# main.net
KiCad netlist of a schematic drawn in EAGLE
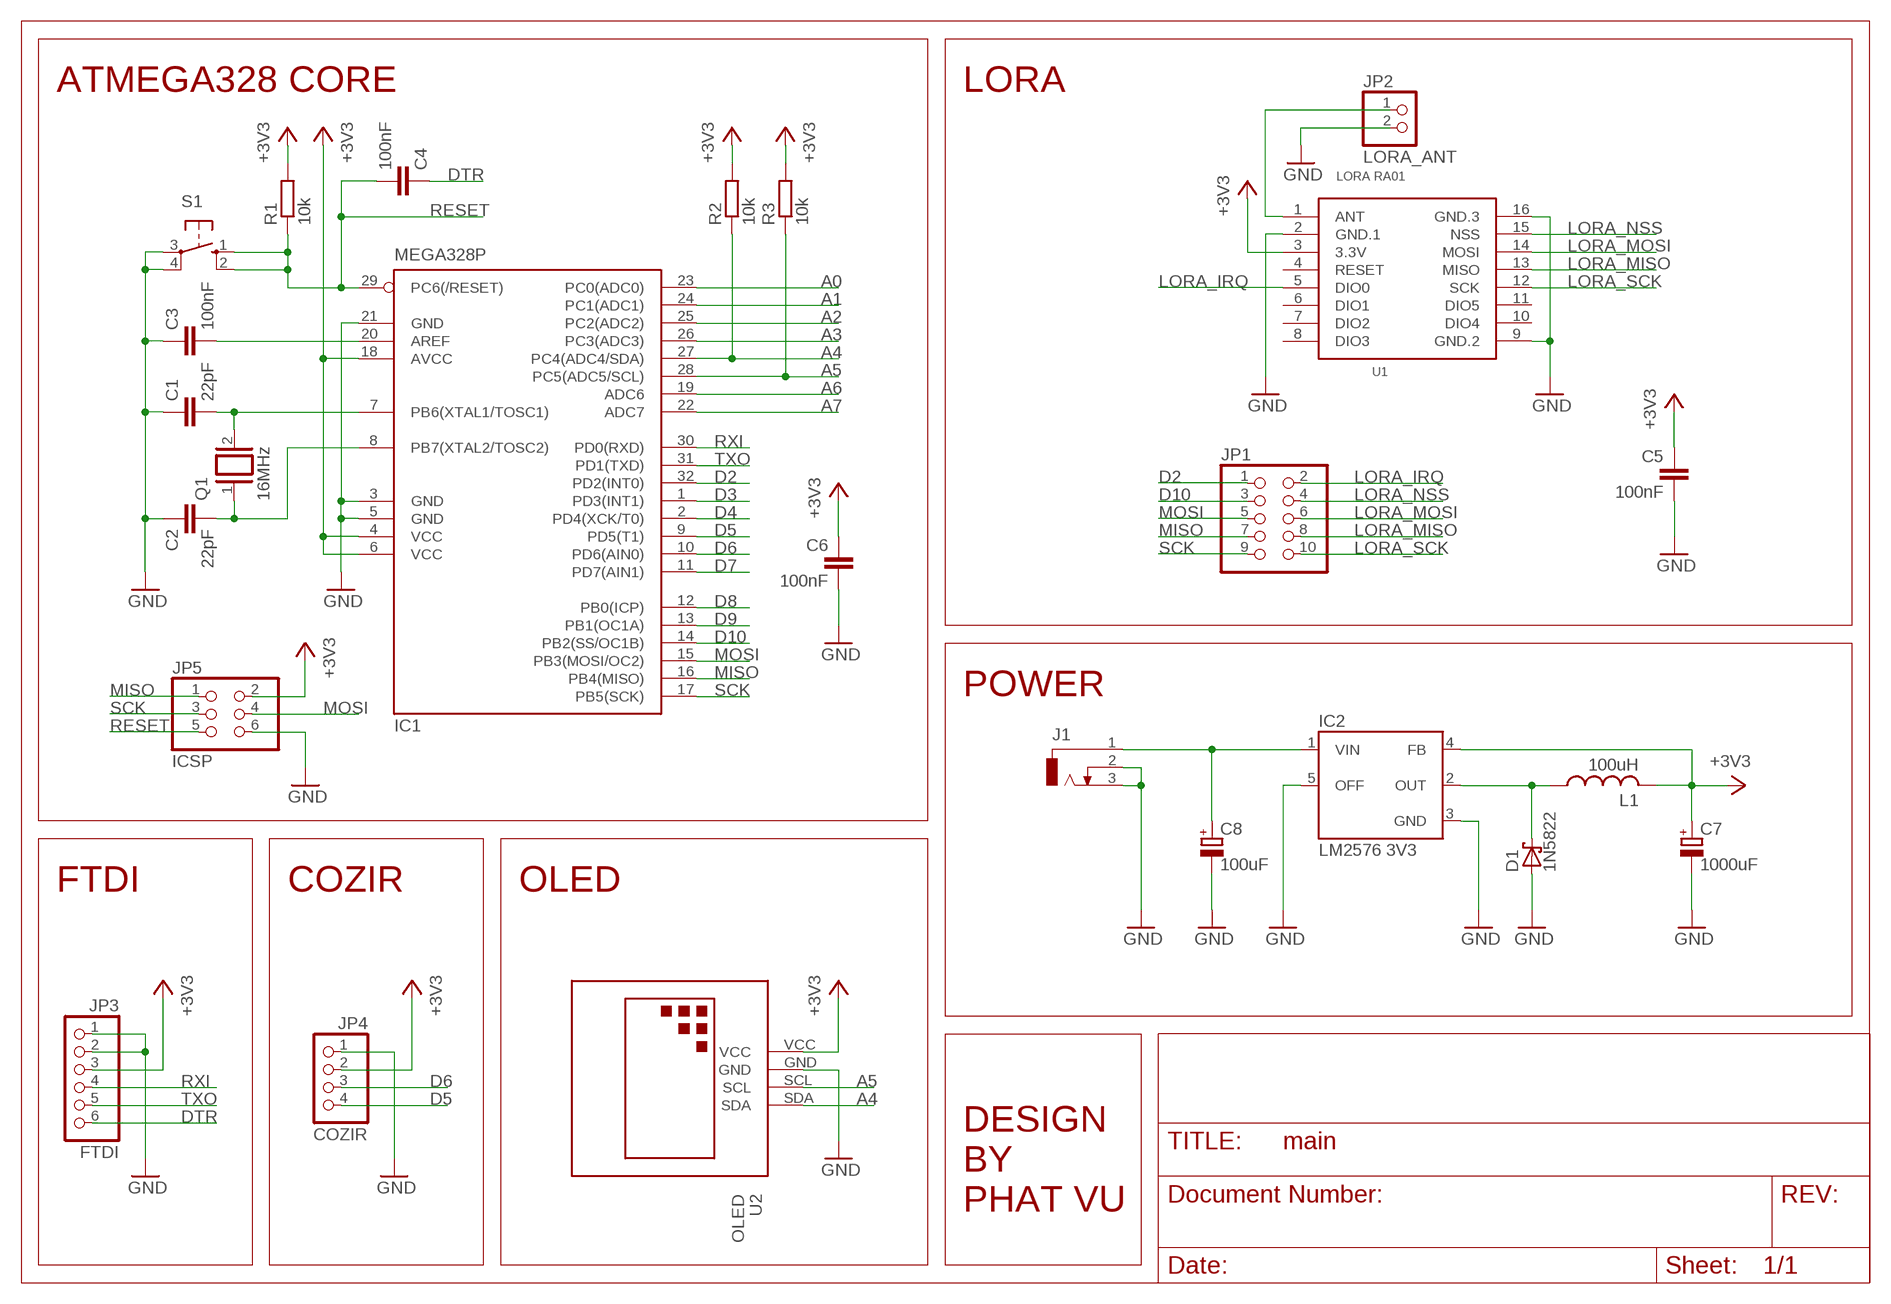
[diagram p0: schematic, sheet 1]

(export (version "E")
  (design (tool "Eeschema 10.0.6"))
  (components
    (comp (ref "C1")
      (value "22pF")
      (footprint "eagle-import:C050-024X044")
      (libsource (lib "eagle-import") (part "C-EU050-024X044"))
    )
    (comp (ref "C2")
      (value "22pF")
      (footprint "eagle-import:C050-024X044")
      (libsource (lib "eagle-import") (part "C-EU050-024X044"))
    )
    (comp (ref "C3")
      (value "100nF")
      (footprint "eagle-import:C050-024X044")
      (libsource (lib "eagle-import") (part "C-EU050-024X044"))
    )
    (comp (ref "C4")
      (value "100nF")
      (footprint "eagle-import:C050-024X044")
      (libsource (lib "eagle-import") (part "C-EU050-024X044"))
    )
    (comp (ref "C5")
      (value "100nF")
      (footprint "eagle-import:C050-024X044")
      (libsource (lib "eagle-import") (part "C-EU050-024X044"))
    )
    (comp (ref "C6")
      (value "100nF")
      (footprint "eagle-import:C050-024X044")
      (libsource (lib "eagle-import") (part "C-EU050-024X044"))
    )
    (comp (ref "C7")
      (value "1000uF")
      (footprint "eagle-import:E5-13")
      (libsource (lib "eagle-import") (part "CPOL-EUE5-13"))
    )
    (comp (ref "C8")
      (value "100uF")
      (footprint "eagle-import:E5-8,5")
      (libsource (lib "eagle-import") (part "CPOL-EUE5-8.5"))
    )
    (comp (ref "D1")
      (value "1N5822")
      (footprint "eagle-import:DO201T15")
      (libsource (lib "eagle-import") (part "SCHOTTKY-DIODEDO201T15"))
    )
    (comp (ref "IC1")
      (value "MEGA328P")
      (footprint "eagle-import:TQFP32-08")
      (fields (field (name "MPN") "ATMEGA8-16AU"))
      (libsource (lib "eagle-import") (part "MEGA8-AI"))
    )
    (comp (ref "IC2")
      (value "LM2576 3V3")
      (footprint "eagle-import:TO263-5")
      (libsource (lib "eagle-import") (part "LM2576S"))
    )
    (comp (ref "J1")
      (value "DCJ0303")
      (footprint "eagle-import:DCJ0303")
      (libsource (lib "eagle-import") (part "DCJ0303"))
    )
    (comp (ref "JP1")
      (value "PINHD-2X5")
      (footprint "eagle-import:2X05")
      (libsource (lib "eagle-import") (part "PINHD-2X5"))
    )
    (comp (ref "JP2")
      (value "LORA_ANT")
      (footprint "eagle-import:1X02")
      (libsource (lib "eagle-import") (part "PINHD-1X2"))
    )
    (comp (ref "JP3")
      (value "FTDI")
      (footprint "eagle-import:1X06")
      (libsource (lib "eagle-import") (part "PINHD-1X6"))
    )
    (comp (ref "JP4")
      (value "COZIR")
      (footprint "eagle-import:1X04")
      (libsource (lib "eagle-import") (part "PINHD-1X4"))
    )
    (comp (ref "JP5")
      (value "ICSP")
      (footprint "eagle-import:2X03")
      (libsource (lib "eagle-import") (part "PINHD-2X3"))
    )
    (comp (ref "L1")
      (value "100uH")
      (footprint "eagle-import:6000-XXXX-RC")
      (libsource (lib "eagle-import") (part "L-US6000-XXX-RC"))
    )
    (comp (ref "Q1")
      (value "16MHz")
      (footprint "eagle-import:QS")
      (libsource (lib "eagle-import") (part "XTAL/S"))
    )
    (comp (ref "R1")
      (value "10k")
      (footprint "eagle-import:0207_10")
      (libsource (lib "eagle-import") (part "R-EU_0207/10"))
    )
    (comp (ref "R2")
      (value "10k")
      (footprint "eagle-import:0207_10")
      (libsource (lib "eagle-import") (part "R-EU_0207/10"))
    )
    (comp (ref "R3")
      (value "10k")
      (footprint "eagle-import:0207_10")
      (libsource (lib "eagle-import") (part "R-EU_0207/10"))
    )
    (comp (ref "S1")
      (value "10-XX")
      (footprint "eagle-import:B3F-10XX")
      (fields (field (name "MPN") "B3F-1000"))
      (libsource (lib "eagle-import") (part "10-XX"))
    )
    (comp (ref "U1")
      (value "LORA RA01")
      (footprint "eagle-import:LORA-RA1-SMD")
      (libsource (lib "eagle-import") (part "LORA-RA-01-433MHZ"))
    )
    (comp (ref "U2")
      (value "OLED")
      (footprint "eagle-import:OLED-096-I2C")
      (libsource (lib "eagle-import") (part "OLED-096-I2C"))
    )
  )
  (nets
    (net (code "1") (name "+3V3") (class "Default")
      (node (ref "C5") (pin "1") (pinfunction "1_1") (pintype "passive"))
      (node (ref "C6") (pin "1") (pinfunction "1_1") (pintype "passive"))
      (node (ref "C7") (pin "+") (pinfunction "+_+") (pintype "passive"))
      (node (ref "IC1") (pin "18") (pinfunction "AVCC_18") (pintype "power_in"))
      (node (ref "IC1") (pin "4") (pinfunction "VCC_4") (pintype "power_in"))
      (node (ref "IC1") (pin "6") (pinfunction "VCC_6") (pintype "power_in"))
      (node (ref "IC2") (pin "4") (pinfunction "FB_4") (pintype "input"))
      (node (ref "JP3") (pin "3") (pinfunction "3_3") (pintype "passive"))
      (node (ref "JP4") (pin "2") (pinfunction "2_2") (pintype "passive"))
      (node (ref "JP5") (pin "2") (pinfunction "2_2") (pintype "passive"))
      (node (ref "L1") (pin "2") (pinfunction "2_2") (pintype "passive"))
      (node (ref "R1") (pin "2") (pinfunction "2_2") (pintype "passive"))
      (node (ref "R2") (pin "2") (pinfunction "2_2") (pintype "passive"))
      (node (ref "R3") (pin "2") (pinfunction "2_2") (pintype "passive"))
      (node (ref "U1") (pin "3") (pinfunction "3.3V_3") (pintype "power_in"))
      (node (ref "U2") (pin "VCC") (pinfunction "VCC_VCC") (pintype "power_in"))
    )
    (net (code "2") (name "/A0") (class "Default")
      (node (ref "IC1") (pin "23") (pinfunction "PC0(ADC0)_23") (pintype "bidirectional"))
    )
    (net (code "3") (name "/A1") (class "Default")
      (node (ref "IC1") (pin "24") (pinfunction "PC1(ADC1)_24") (pintype "bidirectional"))
    )
    (net (code "4") (name "/A2") (class "Default")
      (node (ref "IC1") (pin "25") (pinfunction "PC2(ADC2)_25") (pintype "bidirectional"))
    )
    (net (code "5") (name "/A3") (class "Default")
      (node (ref "IC1") (pin "26") (pinfunction "PC3(ADC3)_26") (pintype "bidirectional"))
    )
    (net (code "6") (name "/A4") (class "Default")
      (node (ref "IC1") (pin "27") (pinfunction "PC4(ADC4/SDA)_27") (pintype "bidirectional"))
      (node (ref "R2") (pin "1") (pinfunction "1_1") (pintype "passive"))
      (node (ref "U2") (pin "SDA") (pinfunction "SDA_SDA") (pintype "bidirectional"))
    )
    (net (code "7") (name "/A5") (class "Default")
      (node (ref "IC1") (pin "28") (pinfunction "PC5(ADC5/SCL)_28") (pintype "bidirectional"))
      (node (ref "R3") (pin "1") (pinfunction "1_1") (pintype "passive"))
      (node (ref "U2") (pin "SCL") (pinfunction "SCL_SCL") (pintype "bidirectional"))
    )
    (net (code "8") (name "/A6") (class "Default")
      (node (ref "IC1") (pin "19") (pinfunction "ADC6_19") (pintype "bidirectional"))
    )
    (net (code "9") (name "/A7") (class "Default")
      (node (ref "IC1") (pin "22") (pinfunction "ADC7_22") (pintype "bidirectional"))
    )
    (net (code "10") (name "/D2") (class "Default")
      (node (ref "IC1") (pin "32") (pinfunction "PD2(INT0)_32") (pintype "bidirectional"))
      (node (ref "JP1") (pin "1") (pinfunction "1_1") (pintype "passive"))
    )
    (net (code "11") (name "/D3") (class "Default")
      (node (ref "IC1") (pin "1") (pinfunction "PD3(INT1)_1") (pintype "bidirectional"))
    )
    (net (code "12") (name "/D4") (class "Default")
      (node (ref "IC1") (pin "2") (pinfunction "PD4(XCK/T0)_2") (pintype "bidirectional"))
    )
    (net (code "13") (name "/D5") (class "Default")
      (node (ref "IC1") (pin "9") (pinfunction "PD5(T1)_9") (pintype "bidirectional"))
      (node (ref "JP4") (pin "4") (pinfunction "4_4") (pintype "passive"))
    )
    (net (code "14") (name "/D6") (class "Default")
      (node (ref "IC1") (pin "10") (pinfunction "PD6(AIN0)_10") (pintype "bidirectional"))
      (node (ref "JP4") (pin "3") (pinfunction "3_3") (pintype "passive"))
    )
    (net (code "15") (name "/D7") (class "Default")
      (node (ref "IC1") (pin "11") (pinfunction "PD7(AIN1)_11") (pintype "bidirectional"))
    )
    (net (code "16") (name "/D8") (class "Default")
      (node (ref "IC1") (pin "12") (pinfunction "PB0(ICP)_12") (pintype "bidirectional"))
    )
    (net (code "17") (name "/D9") (class "Default")
      (node (ref "IC1") (pin "13") (pinfunction "PB1(OC1A)_13") (pintype "bidirectional"))
    )
    (net (code "18") (name "/D10") (class "Default")
      (node (ref "IC1") (pin "14") (pinfunction "PB2(SS/OC1B)_14") (pintype "bidirectional"))
      (node (ref "JP1") (pin "3") (pinfunction "3_3") (pintype "passive"))
    )
    (net (code "19") (name "/DTR") (class "Default")
      (node (ref "C4") (pin "1") (pinfunction "1_1") (pintype "passive"))
      (node (ref "JP3") (pin "6") (pinfunction "6_6") (pintype "passive"))
    )
    (net (code "20") (name "/LORA_IRQ") (class "Default")
      (node (ref "JP1") (pin "2") (pinfunction "2_2") (pintype "passive"))
      (node (ref "U1") (pin "5") (pinfunction "DIO0_5") (pintype "bidirectional"))
    )
    (net (code "21") (name "/LORA_MISO") (class "Default")
      (node (ref "JP1") (pin "8") (pinfunction "8_8") (pintype "passive"))
      (node (ref "U1") (pin "13") (pinfunction "MISO_13") (pintype "bidirectional"))
    )
    (net (code "22") (name "/LORA_MOSI") (class "Default")
      (node (ref "JP1") (pin "6") (pinfunction "6_6") (pintype "passive"))
      (node (ref "U1") (pin "14") (pinfunction "MOSI_14") (pintype "bidirectional"))
    )
    (net (code "23") (name "/LORA_NSS") (class "Default")
      (node (ref "JP1") (pin "4") (pinfunction "4_4") (pintype "passive"))
      (node (ref "U1") (pin "15") (pinfunction "NSS_15") (pintype "bidirectional"))
    )
    (net (code "24") (name "/LORA_SCK") (class "Default")
      (node (ref "JP1") (pin "10") (pinfunction "10_10") (pintype "passive"))
      (node (ref "U1") (pin "12") (pinfunction "SCK_12") (pintype "bidirectional"))
    )
    (net (code "25") (name "/MISO") (class "Default")
      (node (ref "IC1") (pin "16") (pinfunction "PB4(MISO)_16") (pintype "bidirectional"))
      (node (ref "JP1") (pin "7") (pinfunction "7_7") (pintype "passive"))
      (node (ref "JP5") (pin "1") (pinfunction "1_1") (pintype "passive"))
    )
    (net (code "26") (name "/MOSI") (class "Default")
      (node (ref "IC1") (pin "15") (pinfunction "PB3(MOSI/OC2)_15") (pintype "bidirectional"))
      (node (ref "JP1") (pin "5") (pinfunction "5_5") (pintype "passive"))
      (node (ref "JP5") (pin "4") (pinfunction "4_4") (pintype "passive"))
    )
    (net (code "27") (name "/RESET") (class "Default")
      (node (ref "C4") (pin "2") (pinfunction "2_2") (pintype "passive"))
      (node (ref "IC1") (pin "29") (pinfunction "PC6(/RESET)_29") (pintype "bidirectional"))
      (node (ref "JP5") (pin "5") (pinfunction "5_5") (pintype "passive"))
      (node (ref "R1") (pin "1") (pinfunction "1_1") (pintype "passive"))
      (node (ref "S1") (pin "1") (pinfunction "S_1") (pintype "passive"))
      (node (ref "S1") (pin "2") (pinfunction "S1_2") (pintype "passive"))
    )
    (net (code "28") (name "/RXI") (class "Default")
      (node (ref "IC1") (pin "30") (pinfunction "PD0(RXD)_30") (pintype "bidirectional"))
      (node (ref "JP3") (pin "4") (pinfunction "4_4") (pintype "passive"))
    )
    (net (code "29") (name "/SCK") (class "Default")
      (node (ref "IC1") (pin "17") (pinfunction "PB5(SCK)_17") (pintype "bidirectional"))
      (node (ref "JP1") (pin "9") (pinfunction "9_9") (pintype "passive"))
      (node (ref "JP5") (pin "3") (pinfunction "3_3") (pintype "passive"))
    )
    (net (code "30") (name "/TXO") (class "Default")
      (node (ref "IC1") (pin "31") (pinfunction "PD1(TXD)_31") (pintype "bidirectional"))
      (node (ref "JP3") (pin "5") (pinfunction "5_5") (pintype "passive"))
    )
    (net (code "31") (name "GND") (class "Default")
      (node (ref "C1") (pin "1") (pinfunction "1_1") (pintype "passive"))
      (node (ref "C2") (pin "1") (pinfunction "1_1") (pintype "passive"))
      (node (ref "C3") (pin "1") (pinfunction "1_1") (pintype "passive"))
      (node (ref "C5") (pin "2") (pinfunction "2_2") (pintype "passive"))
      (node (ref "C6") (pin "2") (pinfunction "2_2") (pintype "passive"))
      (node (ref "C7") (pin "-") (pinfunction "-_-") (pintype "passive"))
      (node (ref "C8") (pin "-") (pinfunction "-_-") (pintype "passive"))
      (node (ref "D1") (pin "A") (pinfunction "A_A") (pintype "passive"))
      (node (ref "IC1") (pin "21") (pinfunction "GND_21") (pintype "power_in"))
      (node (ref "IC1") (pin "3") (pinfunction "GND_3") (pintype "power_in"))
      (node (ref "IC1") (pin "5") (pinfunction "GND_5") (pintype "power_in"))
      (node (ref "IC2") (pin "3") (pinfunction "GND_3") (pintype "power_in"))
      (node (ref "IC2") (pin "5") (pinfunction "OFF_5") (pintype "input"))
      (node (ref "J1") (pin "2") (pinfunction "2_2") (pintype "passive"))
      (node (ref "J1") (pin "3") (pinfunction "3_3") (pintype "passive"))
      (node (ref "JP2") (pin "2") (pinfunction "2_2") (pintype "passive"))
      (node (ref "JP3") (pin "1") (pinfunction "1_1") (pintype "passive"))
      (node (ref "JP3") (pin "2") (pinfunction "2_2") (pintype "passive"))
      (node (ref "JP4") (pin "1") (pinfunction "1_1") (pintype "passive"))
      (node (ref "JP5") (pin "6") (pinfunction "6_6") (pintype "passive"))
      (node (ref "S1") (pin "3") (pinfunction "P_3") (pintype "passive"))
      (node (ref "S1") (pin "4") (pinfunction "P1_4") (pintype "passive"))
      (node (ref "U1") (pin "16") (pinfunction "GND.3_16") (pintype "power_in"))
      (node (ref "U1") (pin "2") (pinfunction "GND.1_2") (pintype "power_in"))
      (node (ref "U1") (pin "9") (pinfunction "GND.2_9") (pintype "power_in"))
      (node (ref "U2") (pin "GND") (pinfunction "GND_GND") (pintype "power_in"))
    )
    (net (code "32") (name "Net-(IC1-AREF)") (class "Default")
      (node (ref "C3") (pin "2") (pinfunction "2_2") (pintype "passive"))
      (node (ref "IC1") (pin "20") (pinfunction "AREF_20") (pintype "passive"))
    )
    (net (code "33") (name "Net-(IC1-PB6(XTAL1{slash}TOSC1))") (class "Default")
      (node (ref "C1") (pin "2") (pinfunction "2_2") (pintype "passive"))
      (node (ref "IC1") (pin "7") (pinfunction "PB6(XTAL1/TOSC1)_7") (pintype "bidirectional"))
      (node (ref "Q1") (pin "2") (pinfunction "2_2") (pintype "passive"))
    )
    (net (code "34") (name "Net-(IC1-PB7(XTAL2{slash}TOSC2))") (class "Default")
      (node (ref "C2") (pin "2") (pinfunction "2_2") (pintype "passive"))
      (node (ref "IC1") (pin "8") (pinfunction "PB7(XTAL2/TOSC2)_8") (pintype "bidirectional"))
      (node (ref "Q1") (pin "1") (pinfunction "1_1") (pintype "passive"))
    )
    (net (code "35") (name "Net-(IC2-OUT)") (class "Default")
      (node (ref "D1") (pin "C") (pinfunction "C_C") (pintype "passive"))
      (node (ref "IC2") (pin "2") (pinfunction "OUT_2") (pintype "output"))
      (node (ref "L1") (pin "1") (pinfunction "1_1") (pintype "passive"))
    )
    (net (code "36") (name "Net-(IC2-VIN)") (class "Default")
      (node (ref "C8") (pin "+") (pinfunction "+_+") (pintype "passive"))
      (node (ref "IC2") (pin "1") (pinfunction "VIN_1") (pintype "power_in"))
      (node (ref "J1") (pin "1") (pinfunction "1_1") (pintype "passive"))
    )
    (net (code "37") (name "Net-(U1-ANT)") (class "Default")
      (node (ref "JP2") (pin "1") (pinfunction "1_1") (pintype "passive"))
      (node (ref "U1") (pin "1") (pinfunction "ANT_1") (pintype "bidirectional"))
    )
    (net (code "38") (name "unconnected-(U1-DIO1-Pad6)") (class "Default")
      (node (ref "U1") (pin "6") (pinfunction "DIO1_6") (pintype "bidirectional"))
    )
    (net (code "39") (name "unconnected-(U1-DIO2-Pad7)") (class "Default")
      (node (ref "U1") (pin "7") (pinfunction "DIO2_7") (pintype "bidirectional"))
    )
    (net (code "40") (name "unconnected-(U1-DIO3-Pad8)") (class "Default")
      (node (ref "U1") (pin "8") (pinfunction "DIO3_8") (pintype "bidirectional"))
    )
    (net (code "41") (name "unconnected-(U1-DIO4-Pad10)") (class "Default")
      (node (ref "U1") (pin "10") (pinfunction "DIO4_10") (pintype "bidirectional"))
    )
    (net (code "42") (name "unconnected-(U1-DIO5-Pad11)") (class "Default")
      (node (ref "U1") (pin "11") (pinfunction "DIO5_11") (pintype "bidirectional"))
    )
    (net (code "43") (name "unconnected-(U1-RESET-Pad4)") (class "Default")
      (node (ref "U1") (pin "4") (pinfunction "RESET_4") (pintype "bidirectional"))
    )
  )
)
